# stm32_schematic.net
KiCad netlist of a schematic drawn in Altium Designer
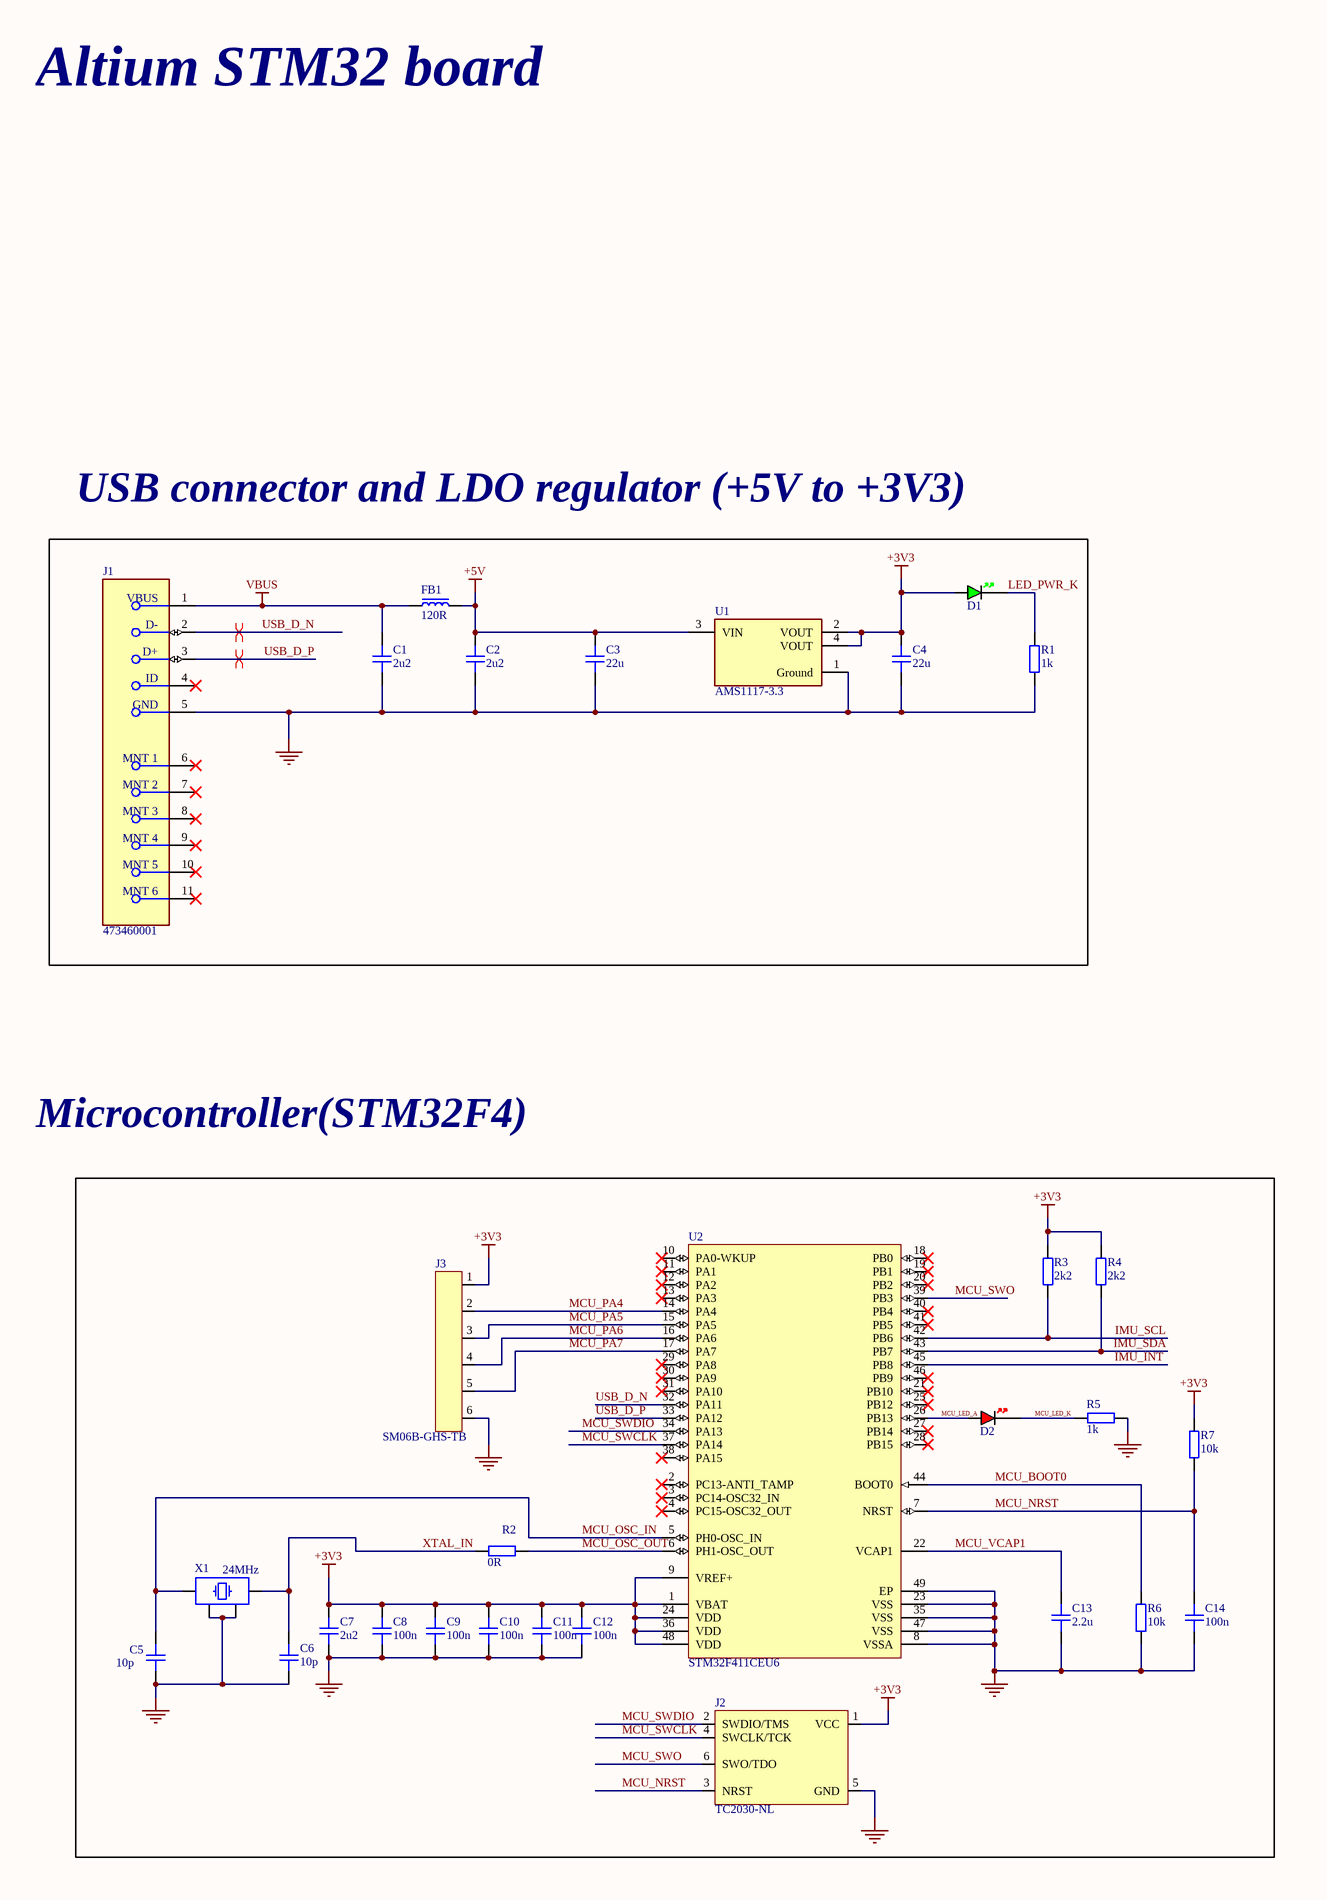
[diagram p0: stm32_schematic.SchDoc, left]
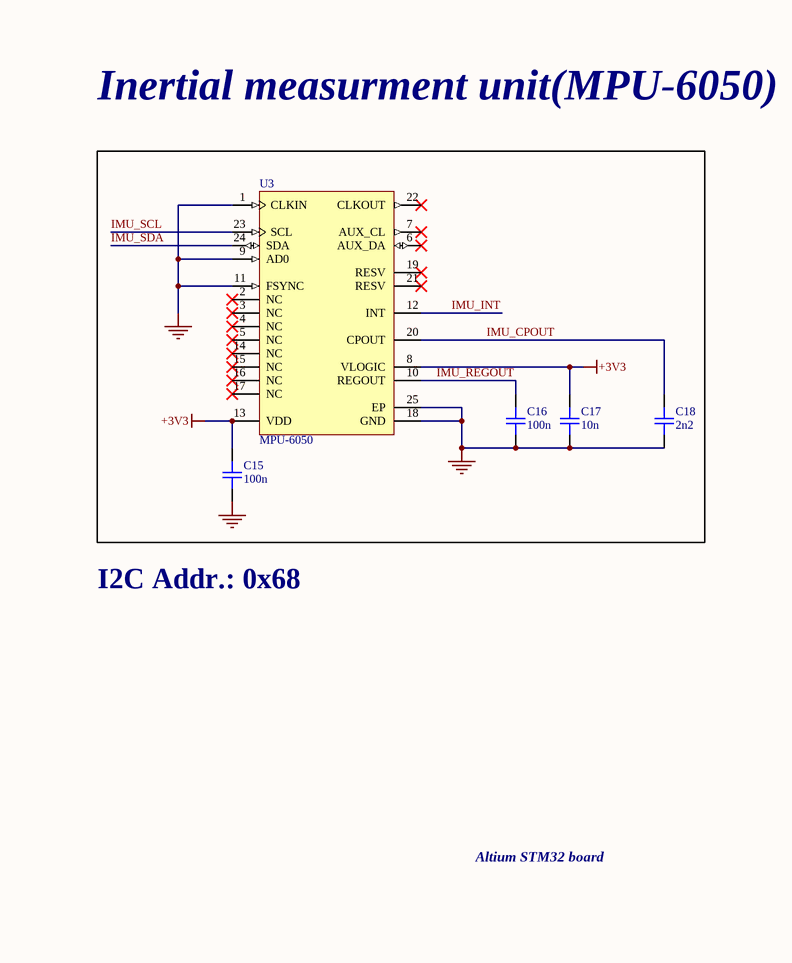
[diagram p1: stm32_schematic.SchDoc, right]

(export (version "E")
  (design (tool "Eeschema 10.0.6"))
  (components
    (comp (ref "C1")
      (value "2u2")
      (footprint "CAP_0603")
      (description "Capacitor SMD 0603")
      (libsource (lib "Schematic-Lib-PhilsLab") (part "CAP_0603"))
    )
    (comp (ref "C2")
      (value "2u2")
      (footprint "CAP_0603")
      (description "Capacitor SMD 0603")
      (libsource (lib "Schematic-Lib-PhilsLab") (part "CAP_0603"))
    )
    (comp (ref "C3")
      (value "22u")
      (footprint "CAP_0805")
      (description "Capacitor SMD 0805")
      (libsource (lib "Schematic-Lib-PhilsLab") (part "CAP_0805"))
    )
    (comp (ref "C4")
      (value "22u")
      (footprint "CAP_0805")
      (description "Capacitor SMD 0805")
      (libsource (lib "Schematic-Lib-PhilsLab") (part "CAP_0805"))
    )
    (comp (ref "C5")
      (value "10p")
      (footprint "CAP_0402")
      (description "Capacitor SMD 0402")
      (libsource (lib "Schematic-Lib-PhilsLab") (part "CAP_0402"))
    )
    (comp (ref "C6")
      (value "10p")
      (footprint "CAP_0402")
      (description "Capacitor SMD 0402")
      (libsource (lib "Schematic-Lib-PhilsLab") (part "CAP_0402"))
    )
    (comp (ref "C7")
      (value "2u2")
      (footprint "CAP_0603")
      (description "Capacitor SMD 0603")
      (libsource (lib "Schematic-Lib-PhilsLab") (part "CAP_0603"))
    )
    (comp (ref "C8")
      (value "100n")
      (footprint "CAP_0402")
      (description "Capacitor SMD 0402")
      (libsource (lib "Schematic-Lib-PhilsLab") (part "CAP_0402"))
    )
    (comp (ref "C9")
      (value "100n")
      (footprint "CAP_0402")
      (description "Capacitor SMD 0402")
      (libsource (lib "Schematic-Lib-PhilsLab") (part "CAP_0402"))
    )
    (comp (ref "C10")
      (value "100n")
      (footprint "CAP_0402")
      (description "Capacitor SMD 0402")
      (libsource (lib "Schematic-Lib-PhilsLab") (part "CAP_0402"))
    )
    (comp (ref "C11")
      (value "100n")
      (footprint "CAP_0402")
      (description "Capacitor SMD 0402")
      (libsource (lib "Schematic-Lib-PhilsLab") (part "CAP_0402"))
    )
    (comp (ref "C12")
      (value "100n")
      (footprint "CAP_0402")
      (description "Capacitor SMD 0402")
      (libsource (lib "Schematic-Lib-PhilsLab") (part "CAP_0402"))
    )
    (comp (ref "C13")
      (value "2.2u")
      (footprint "CAP_0603")
      (description "Capacitor SMD 0603")
      (libsource (lib "Schematic-Lib-PhilsLab") (part "CAP_0603"))
    )
    (comp (ref "C14")
      (value "100n")
      (footprint "CAP_0402")
      (description "Capacitor SMD 0402")
      (libsource (lib "Schematic-Lib-PhilsLab") (part "CAP_0402"))
    )
    (comp (ref "C15")
      (value "100n")
      (footprint "CAP_0402")
      (description "Capacitor SMD 0402")
      (libsource (lib "Schematic-Lib-PhilsLab") (part "CAP_0402"))
    )
    (comp (ref "C16")
      (value "100n")
      (footprint "CAP_0402")
      (description "Capacitor SMD 0402")
      (libsource (lib "Schematic-Lib-PhilsLab") (part "CAP_0402"))
    )
    (comp (ref "C17")
      (value "10n")
      (footprint "CAP_0402")
      (description "Capacitor SMD 0402")
      (libsource (lib "Schematic-Lib-PhilsLab") (part "CAP_0402"))
    )
    (comp (ref "C18")
      (value "2n2")
      (footprint "CAP_0402")
      (description "Capacitor SMD 0402")
      (libsource (lib "Schematic-Lib-PhilsLab") (part "CAP_0402"))
    )
    (comp (ref "D1")
      (value "GREEN")
      (footprint "LED_0402_GREEN")
      (description "LED 0402 GREEN SMD")
      (libsource (lib "Schematic-Lib-PhilsLab") (part "LED_0402_GREEN"))
    )
    (comp (ref "D2")
      (value "RED")
      (footprint "LED_0402_RED")
      (description "LED 0402 RED SMD")
      (libsource (lib "Schematic-Lib-PhilsLab") (part "LED_0402_RED"))
    )
    (comp (ref "FB1")
      (value "120R")
      (footprint "FB_0603")
      (description "Ferrite Bead SMD 0603")
      (libsource (lib "Schematic-Lib-PhilsLab") (part "FB_0603"))
    )
    (comp (ref "J1")
      (value "473460001")
      (footprint "FP-473460001-MFG")
      (description "CONN RCPT USB2.0 MICRO B SMD R/A")
      (fields
        (field (name "OCTOPART") "https://octopart.com/47346-0001-molex-7164928")
        (field (name "MANUFACTURER") "Molex")
      )
      (libsource (lib "Altium Content Vault") (part "53ae1f1d9b557310b43ca686e5bb76a"))
    )
    (comp (ref "J2")
      (value "TC2030-NL")
      (footprint "TC2030-NL-FP")
      (description "Tag-Connect No-Solder SWD Debug Connector (No Legs) DO NOT PLACE")
      (fields
        (field (name "MANUFACTURER") "Tag-Connect")
        (field (name "MANUFACTURER PART NUMBER") "TC2030-NL-FP")
      )
      (libsource (lib "Schematic-Lib-PhilsLab") (part "TC2030-NL"))
    )
    (comp (ref "J3")
      (value "SM06B-GHS-TB")
      (footprint "SM06B-GHS-TB")
      (description "Header Connector 6 Position 1.25MM Pitch SMD Horizontal JST GH")
      (fields (field (name "MANUFACTURER") "JST"))
      (libsource (lib "Schematic-Lib-PhilsLab") (part "SM06B-GHS-TB"))
    )
    (comp (ref "R1")
      (value "1k")
      (footprint "RES_0402")
      (description "Resistor SMD 0402")
      (libsource (lib "Schematic-Lib-PhilsLab") (part "RES_0402"))
    )
    (comp (ref "R2")
      (value "0R")
      (footprint "RES_0402")
      (description "Resistor SMD 0402")
      (libsource (lib "Schematic-Lib-PhilsLab") (part "RES_0402"))
    )
    (comp (ref "R3")
      (value "2k2")
      (footprint "RES_0402")
      (description "Resistor SMD 0402")
      (libsource (lib "Schematic-Lib-PhilsLab") (part "RES_0402"))
    )
    (comp (ref "R4")
      (value "2k2")
      (footprint "RES_0402")
      (description "Resistor SMD 0402")
      (libsource (lib "Schematic-Lib-PhilsLab") (part "RES_0402"))
    )
    (comp (ref "R5")
      (value "1k")
      (footprint "RES_0402")
      (description "Resistor SMD 0402")
      (libsource (lib "Schematic-Lib-PhilsLab") (part "RES_0402"))
    )
    (comp (ref "R6")
      (value "10k")
      (footprint "RES_0402")
      (description "Resistor SMD 0402")
      (libsource (lib "Schematic-Lib-PhilsLab") (part "RES_0402"))
    )
    (comp (ref "R7")
      (value "10k")
      (footprint "RES_0402")
      (description "Resistor SMD 0402")
      (libsource (lib "Schematic-Lib-PhilsLab") (part "RES_0402"))
    )
    (comp (ref "U1")
      (value "AMS1117-3.3")
      (footprint "FP-AMS1117-IPC_C")
      (description "LDO Voltage Regulators 1A, 3.3V")
      (fields
        (field (name "OCTOPART") "https://octopart.com/ams1117-3.3-advanced+monolithic+systems-25899300")
        (field (name "MANUFACTURER") "Advanced Monolithic Systems")
      )
      (libsource (lib "Altium Content Vault") (part "8bdbb5f8e77002000e30dd2845d0354"))
    )
    (comp (ref "U2")
      (value "STM32F411CEU6")
      (footprint "STM-UFQFPN48_L")
      (libsource (lib "Altium Content Vault") (part "MC-ARM-STM32F411-UFQFPN48"))
    )
    (comp (ref "U3")
      (value "MPU-6050")
      (footprint "IS-QFN-24_V")
      (fields (field (name "MANUFACTURER") "InvenSense"))
      (libsource (lib "Altium Content Vault") (part "IS-MPU-6050-QFN-24"))
    )
    (comp (ref "X1")
      (value "24MHz")
      (footprint "XTAL_3225")
      (description "Crystal SMD 24MHz 10PPM 7pF 3225")
      (fields
        (field (name "MANUFACTURER") "Epson")
        (field (name "MANUFACTURER PART NUMBER") "TSX-3225 24.0000MF15X-AC")
      )
      (libsource (lib "Schematic-Lib-PhilsLab") (part "TSX-3225_24.0000MF15X-AC"))
    )
  )
  (nets
    (net (code "1") (name "+3V3") (class "Default")
      (node (ref "C10") (pin "2") (pinfunction "2_2") (pintype "passive"))
      (node (ref "C11") (pin "2") (pinfunction "2_2") (pintype "passive"))
      (node (ref "C12") (pin "2") (pinfunction "2_2") (pintype "passive"))
      (node (ref "C15") (pin "2") (pinfunction "2_2") (pintype "passive"))
      (node (ref "C17") (pin "2") (pinfunction "2_2") (pintype "passive"))
      (node (ref "C4") (pin "2") (pinfunction "2_2") (pintype "passive"))
      (node (ref "C7") (pin "2") (pinfunction "2_2") (pintype "passive"))
      (node (ref "C8") (pin "2") (pinfunction "2_2") (pintype "passive"))
      (node (ref "C9") (pin "2") (pinfunction "2_2") (pintype "passive"))
      (node (ref "D1") (pin "A") (pinfunction "A_A") (pintype "passive"))
      (node (ref "J2") (pin "1") (pinfunction "VCC_1") (pintype "passive"))
      (node (ref "J3") (pin "1") (pinfunction "1_1") (pintype "passive"))
      (node (ref "R3") (pin "2") (pinfunction "2_2") (pintype "passive"))
      (node (ref "R4") (pin "2") (pinfunction "2_2") (pintype "passive"))
      (node (ref "R7") (pin "2") (pinfunction "2_2") (pintype "passive"))
      (node (ref "U1") (pin "2") (pinfunction "VOUT_2") (pintype "passive"))
      (node (ref "U1") (pin "4") (pinfunction "VOUT_4") (pintype "passive"))
      (node (ref "U2") (pin "1") (pinfunction "VBAT_1") (pintype "power_in"))
      (node (ref "U2") (pin "24") (pinfunction "VDD_24") (pintype "power_in"))
      (node (ref "U2") (pin "36") (pinfunction "VDD_36") (pintype "power_in"))
      (node (ref "U2") (pin "48") (pinfunction "VDD_48") (pintype "power_in"))
      (node (ref "U2") (pin "9") (pinfunction "VREF+_9") (pintype "power_in"))
      (node (ref "U3") (pin "13") (pinfunction "VDD_13") (pintype "power_in"))
      (node (ref "U3") (pin "8") (pinfunction "VLOGIC_8") (pintype "power_in"))
    )
    (net (code "2") (name "+5V") (class "Default")
      (node (ref "C2") (pin "2") (pinfunction "2_2") (pintype "passive"))
      (node (ref "C3") (pin "2") (pinfunction "2_2") (pintype "passive"))
      (node (ref "FB1") (pin "2") (pinfunction "2_2") (pintype "passive"))
      (node (ref "U1") (pin "3") (pinfunction "VIN_3") (pintype "power_in"))
    )
    (net (code "4") (name "/IMU_CPOUT") (class "Default")
      (node (ref "C18") (pin "2") (pinfunction "2_2") (pintype "passive"))
      (node (ref "U3") (pin "20") (pinfunction "CPOUT_20") (pintype "passive"))
    )
    (net (code "5") (name "/IMU_INT") (class "Default")
      (node (ref "U2") (pin "45") (pinfunction "PB8_45") (pintype "bidirectional"))
      (node (ref "U3") (pin "12") (pinfunction "INT_12") (pintype "open_collector"))
    )
    (net (code "6") (name "/IMU_REGOUT") (class "Default")
      (node (ref "C16") (pin "2") (pinfunction "2_2") (pintype "passive"))
      (node (ref "U3") (pin "10") (pinfunction "REGOUT_10") (pintype "passive"))
    )
    (net (code "7") (name "/IMU_SCL") (class "Default")
      (node (ref "R3") (pin "1") (pinfunction "1_1") (pintype "passive"))
      (node (ref "U2") (pin "42") (pinfunction "PB6_42") (pintype "bidirectional"))
      (node (ref "U3") (pin "23") (pinfunction "SCL_23") (pintype "input"))
    )
    (net (code "8") (name "/IMU_SDA") (class "Default")
      (node (ref "R4") (pin "1") (pinfunction "1_1") (pintype "passive"))
      (node (ref "U2") (pin "43") (pinfunction "PB7_43") (pintype "bidirectional"))
      (node (ref "U3") (pin "24") (pinfunction "SDA_24") (pintype "bidirectional"))
    )
    (net (code "9") (name "/LED_PWR_K") (class "Default")
      (node (ref "D1") (pin "K") (pinfunction "K_K") (pintype "passive"))
      (node (ref "R1") (pin "2") (pinfunction "2_2") (pintype "passive"))
    )
    (net (code "10") (name "/MCU_BOOT0") (class "Default")
      (node (ref "R6") (pin "2") (pinfunction "2_2") (pintype "passive"))
      (node (ref "U2") (pin "44") (pinfunction "BOOT0_44") (pintype "input"))
    )
    (net (code "11") (name "/MCU_LED_A") (class "Default")
      (node (ref "D2") (pin "A") (pinfunction "A_A") (pintype "passive"))
      (node (ref "U2") (pin "26") (pinfunction "PB13_26") (pintype "bidirectional"))
    )
    (net (code "12") (name "/MCU_LED_K") (class "Default")
      (node (ref "D2") (pin "K") (pinfunction "K_K") (pintype "passive"))
      (node (ref "R5") (pin "2") (pinfunction "2_2") (pintype "passive"))
    )
    (net (code "13") (name "/MCU_NRST") (class "Default")
      (node (ref "C14") (pin "2") (pinfunction "2_2") (pintype "passive"))
      (node (ref "J2") (pin "3") (pinfunction "NRST_3") (pintype "passive"))
      (node (ref "R7") (pin "1") (pinfunction "1_1") (pintype "passive"))
      (node (ref "U2") (pin "7") (pinfunction "NRST_7") (pintype "bidirectional"))
    )
    (net (code "14") (name "/MCU_OSC_IN") (class "Default")
      (node (ref "C5") (pin "2") (pinfunction "2_2") (pintype "passive"))
      (node (ref "U2") (pin "5") (pinfunction "PH0-OSC_IN_5") (pintype "bidirectional"))
      (node (ref "X1") (pin "1") (pinfunction "1_1") (pintype "passive"))
    )
    (net (code "15") (name "/MCU_OSC_OUT") (class "Default")
      (node (ref "R2") (pin "2") (pinfunction "2_2") (pintype "passive"))
      (node (ref "U2") (pin "6") (pinfunction "PH1-OSC_OUT_6") (pintype "bidirectional"))
    )
    (net (code "16") (name "/MCU_PA4") (class "Default")
      (node (ref "J3") (pin "2") (pinfunction "2_2") (pintype "passive"))
      (node (ref "U2") (pin "14") (pinfunction "PA4_14") (pintype "bidirectional"))
    )
    (net (code "17") (name "/MCU_PA5") (class "Default")
      (node (ref "J3") (pin "3") (pinfunction "3_3") (pintype "passive"))
      (node (ref "U2") (pin "15") (pinfunction "PA5_15") (pintype "bidirectional"))
    )
    (net (code "18") (name "/MCU_PA6") (class "Default")
      (node (ref "J3") (pin "4") (pinfunction "4_4") (pintype "passive"))
      (node (ref "U2") (pin "16") (pinfunction "PA6_16") (pintype "bidirectional"))
    )
    (net (code "19") (name "/MCU_PA7") (class "Default")
      (node (ref "J3") (pin "5") (pinfunction "5_5") (pintype "passive"))
      (node (ref "U2") (pin "17") (pinfunction "PA7_17") (pintype "bidirectional"))
    )
    (net (code "20") (name "/MCU_SWCLK") (class "Default")
      (node (ref "J2") (pin "4") (pinfunction "SWCLK/TCK_4") (pintype "passive"))
      (node (ref "U2") (pin "37") (pinfunction "PA14_37") (pintype "bidirectional"))
    )
    (net (code "21") (name "/MCU_SWDIO") (class "Default")
      (node (ref "J2") (pin "2") (pinfunction "SWDIO/TMS_2") (pintype "passive"))
      (node (ref "U2") (pin "34") (pinfunction "PA13_34") (pintype "bidirectional"))
    )
    (net (code "22") (name "/MCU_SWO") (class "Default")
      (node (ref "J2") (pin "6") (pinfunction "SWO/TDO_6") (pintype "passive"))
      (node (ref "U2") (pin "39") (pinfunction "PB3_39") (pintype "bidirectional"))
    )
    (net (code "23") (name "/MCU_VCAP1") (class "Default")
      (node (ref "C13") (pin "2") (pinfunction "2_2") (pintype "passive"))
      (node (ref "U2") (pin "22") (pinfunction "VCAP1_22") (pintype "passive"))
    )
    (net (code "24") (name "/USB_D_N") (class "Default")
      (node (ref "J1") (pin "2") (pinfunction "D-_2") (pintype "bidirectional"))
      (node (ref "U2") (pin "32") (pinfunction "PA11_32") (pintype "bidirectional"))
    )
    (net (code "25") (name "/USB_D_P") (class "Default")
      (node (ref "J1") (pin "3") (pinfunction "D+_3") (pintype "bidirectional"))
      (node (ref "U2") (pin "33") (pinfunction "PA12_33") (pintype "bidirectional"))
    )
    (net (code "26") (name "/XTAL_IN") (class "Default")
      (node (ref "C6") (pin "2") (pinfunction "2_2") (pintype "passive"))
      (node (ref "R2") (pin "1") (pinfunction "1_1") (pintype "passive"))
      (node (ref "X1") (pin "3") (pinfunction "3_3") (pintype "passive"))
    )
    (net (code "27") (name "GND") (class "Default")
      (node (ref "C1") (pin "1") (pinfunction "1_1") (pintype "passive"))
      (node (ref "C10") (pin "1") (pinfunction "1_1") (pintype "passive"))
      (node (ref "C11") (pin "1") (pinfunction "1_1") (pintype "passive"))
      (node (ref "C12") (pin "1") (pinfunction "1_1") (pintype "passive"))
      (node (ref "C13") (pin "1") (pinfunction "1_1") (pintype "passive"))
      (node (ref "C14") (pin "1") (pinfunction "1_1") (pintype "passive"))
      (node (ref "C15") (pin "1") (pinfunction "1_1") (pintype "passive"))
      (node (ref "C16") (pin "1") (pinfunction "1_1") (pintype "passive"))
      (node (ref "C17") (pin "1") (pinfunction "1_1") (pintype "passive"))
      (node (ref "C18") (pin "1") (pinfunction "1_1") (pintype "passive"))
      (node (ref "C2") (pin "1") (pinfunction "1_1") (pintype "passive"))
      (node (ref "C3") (pin "1") (pinfunction "1_1") (pintype "passive"))
      (node (ref "C4") (pin "1") (pinfunction "1_1") (pintype "passive"))
      (node (ref "C5") (pin "1") (pinfunction "1_1") (pintype "passive"))
      (node (ref "C6") (pin "1") (pinfunction "1_1") (pintype "passive"))
      (node (ref "C7") (pin "1") (pinfunction "1_1") (pintype "passive"))
      (node (ref "C8") (pin "1") (pinfunction "1_1") (pintype "passive"))
      (node (ref "C9") (pin "1") (pinfunction "1_1") (pintype "passive"))
      (node (ref "J1") (pin "5") (pinfunction "GND_5") (pintype "power_in"))
      (node (ref "J2") (pin "5") (pinfunction "GND_5") (pintype "passive"))
      (node (ref "J3") (pin "6") (pinfunction "6_6") (pintype "passive"))
      (node (ref "R1") (pin "1") (pinfunction "1_1") (pintype "passive"))
      (node (ref "R5") (pin "1") (pinfunction "1_1") (pintype "passive"))
      (node (ref "R6") (pin "1") (pinfunction "1_1") (pintype "passive"))
      (node (ref "U1") (pin "1") (pinfunction "Ground_1") (pintype "power_in"))
      (node (ref "U2") (pin "23") (pinfunction "VSS_23") (pintype "power_in"))
      (node (ref "U2") (pin "35") (pinfunction "VSS_35") (pintype "power_in"))
      (node (ref "U2") (pin "47") (pinfunction "VSS_47") (pintype "power_in"))
      (node (ref "U2") (pin "49") (pinfunction "EP_49") (pintype "power_in"))
      (node (ref "U2") (pin "8") (pinfunction "VSSA_8") (pintype "power_in"))
      (node (ref "U3") (pin "1") (pinfunction "CLKIN_1") (pintype "input"))
      (node (ref "U3") (pin "11") (pinfunction "FSYNC_11") (pintype "input"))
      (node (ref "U3") (pin "18") (pinfunction "GND_18") (pintype "power_in"))
      (node (ref "U3") (pin "25") (pinfunction "EP_25") (pintype "power_in"))
      (node (ref "U3") (pin "9") (pinfunction "AD0_9") (pintype "input"))
      (node (ref "X1") (pin "2") (pinfunction "2_2") (pintype "passive"))
      (node (ref "X1") (pin "4") (pinfunction "4_4") (pintype "passive"))
    )
    (net (code "28") (name "VBUS") (class "Default")
      (node (ref "C1") (pin "2") (pinfunction "2_2") (pintype "passive"))
      (node (ref "FB1") (pin "1") (pinfunction "1_1") (pintype "passive"))
      (node (ref "J1") (pin "1") (pinfunction "VBUS_1") (pintype "power_in"))
    )
    (net (code "29") (name "unconnected-(J1-ID-Pad4)") (class "Default")
      (node (ref "J1") (pin "4") (pinfunction "ID_4") (pintype "passive+no_connect"))
    )
    (net (code "30") (name "unconnected-(J1-MNT_1-Pad6)") (class "Default")
      (node (ref "J1") (pin "6") (pinfunction "MNT_1_6") (pintype "passive+no_connect"))
    )
    (net (code "31") (name "unconnected-(J1-MNT_2-Pad7)") (class "Default")
      (node (ref "J1") (pin "7") (pinfunction "MNT_2_7") (pintype "passive+no_connect"))
    )
    (net (code "32") (name "unconnected-(J1-MNT_3-Pad8)") (class "Default")
      (node (ref "J1") (pin "8") (pinfunction "MNT_3_8") (pintype "passive+no_connect"))
    )
    (net (code "33") (name "unconnected-(J1-MNT_4-Pad9)") (class "Default")
      (node (ref "J1") (pin "9") (pinfunction "MNT_4_9") (pintype "passive+no_connect"))
    )
    (net (code "34") (name "unconnected-(J1-MNT_5-Pad10)") (class "Default")
      (node (ref "J1") (pin "10") (pinfunction "MNT_5_10") (pintype "passive+no_connect"))
    )
    (net (code "35") (name "unconnected-(J1-MNT_6-Pad11)") (class "Default")
      (node (ref "J1") (pin "11") (pinfunction "MNT_6_11") (pintype "passive+no_connect"))
    )
    (net (code "36") (name "unconnected-(U2-PA0-WKUP-Pad10)") (class "Default")
      (node (ref "U2") (pin "10") (pinfunction "PA0-WKUP_10") (pintype "bidirectional+no_connect"))
    )
    (net (code "37") (name "unconnected-(U2-PA1-Pad11)") (class "Default")
      (node (ref "U2") (pin "11") (pinfunction "PA1_11") (pintype "bidirectional+no_connect"))
    )
    (net (code "38") (name "unconnected-(U2-PA2-Pad12)") (class "Default")
      (node (ref "U2") (pin "12") (pinfunction "PA2_12") (pintype "bidirectional+no_connect"))
    )
    (net (code "39") (name "unconnected-(U2-PA3-Pad13)") (class "Default")
      (node (ref "U2") (pin "13") (pinfunction "PA3_13") (pintype "bidirectional+no_connect"))
    )
    (net (code "40") (name "unconnected-(U2-PA8-Pad29)") (class "Default")
      (node (ref "U2") (pin "29") (pinfunction "PA8_29") (pintype "bidirectional+no_connect"))
    )
    (net (code "41") (name "unconnected-(U2-PA9-Pad30)") (class "Default")
      (node (ref "U2") (pin "30") (pinfunction "PA9_30") (pintype "bidirectional+no_connect"))
    )
    (net (code "42") (name "unconnected-(U2-PA10-Pad31)") (class "Default")
      (node (ref "U2") (pin "31") (pinfunction "PA10_31") (pintype "bidirectional+no_connect"))
    )
    (net (code "43") (name "unconnected-(U2-PA15-Pad38)") (class "Default")
      (node (ref "U2") (pin "38") (pinfunction "PA15_38") (pintype "bidirectional+no_connect"))
    )
    (net (code "44") (name "unconnected-(U2-PB0-Pad18)") (class "Default")
      (node (ref "U2") (pin "18") (pinfunction "PB0_18") (pintype "bidirectional+no_connect"))
    )
    (net (code "45") (name "unconnected-(U2-PB1-Pad19)") (class "Default")
      (node (ref "U2") (pin "19") (pinfunction "PB1_19") (pintype "bidirectional+no_connect"))
    )
    (net (code "46") (name "unconnected-(U2-PB2-Pad20)") (class "Default")
      (node (ref "U2") (pin "20") (pinfunction "PB2_20") (pintype "bidirectional+no_connect"))
    )
    (net (code "47") (name "unconnected-(U2-PB4-Pad40)") (class "Default")
      (node (ref "U2") (pin "40") (pinfunction "PB4_40") (pintype "bidirectional+no_connect"))
    )
    (net (code "48") (name "unconnected-(U2-PB5-Pad41)") (class "Default")
      (node (ref "U2") (pin "41") (pinfunction "PB5_41") (pintype "bidirectional+no_connect"))
    )
    (net (code "49") (name "unconnected-(U2-PB9-Pad46)") (class "Default")
      (node (ref "U2") (pin "46") (pinfunction "PB9_46") (pintype "bidirectional+no_connect"))
    )
    (net (code "50") (name "unconnected-(U2-PB10-Pad21)") (class "Default")
      (node (ref "U2") (pin "21") (pinfunction "PB10_21") (pintype "bidirectional+no_connect"))
    )
    (net (code "51") (name "unconnected-(U2-PB12-Pad25)") (class "Default")
      (node (ref "U2") (pin "25") (pinfunction "PB12_25") (pintype "bidirectional+no_connect"))
    )
    (net (code "52") (name "unconnected-(U2-PB14-Pad27)") (class "Default")
      (node (ref "U2") (pin "27") (pinfunction "PB14_27") (pintype "bidirectional+no_connect"))
    )
    (net (code "53") (name "unconnected-(U2-PB15-Pad28)") (class "Default")
      (node (ref "U2") (pin "28") (pinfunction "PB15_28") (pintype "bidirectional+no_connect"))
    )
    (net (code "54") (name "unconnected-(U2-PC13-ANTI_TAMP-Pad2)") (class "Default")
      (node (ref "U2") (pin "2") (pinfunction "PC13-ANTI_TAMP_2") (pintype "bidirectional+no_connect"))
    )
    (net (code "55") (name "unconnected-(U2-PC14-OSC32_IN-Pad3)") (class "Default")
      (node (ref "U2") (pin "3") (pinfunction "PC14-OSC32_IN_3") (pintype "bidirectional+no_connect"))
    )
    (net (code "56") (name "unconnected-(U2-PC15-OSC32_OUT-Pad4)") (class "Default")
      (node (ref "U2") (pin "4") (pinfunction "PC15-OSC32_OUT_4") (pintype "bidirectional+no_connect"))
    )
    (net (code "57") (name "unconnected-(U3-AUX_CL-Pad7)") (class "Default")
      (node (ref "U3") (pin "7") (pinfunction "AUX_CL_7") (pintype "output+no_connect"))
    )
    (net (code "58") (name "unconnected-(U3-AUX_DA-Pad6)") (class "Default")
      (node (ref "U3") (pin "6") (pinfunction "AUX_DA_6") (pintype "bidirectional+no_connect"))
    )
    (net (code "59") (name "unconnected-(U3-CLKOUT-Pad22)") (class "Default")
      (node (ref "U3") (pin "22") (pinfunction "CLKOUT_22") (pintype "output+no_connect"))
    )
    (net (code "60") (name "unconnected-(U3-NC-Pad2)") (class "Default")
      (node (ref "U3") (pin "2") (pinfunction "NC_2") (pintype "passive+no_connect"))
    )
    (net (code "61") (name "unconnected-(U3-NC-Pad3)") (class "Default")
      (node (ref "U3") (pin "3") (pinfunction "NC_3") (pintype "passive+no_connect"))
    )
    (net (code "62") (name "unconnected-(U3-NC-Pad4)") (class "Default")
      (node (ref "U3") (pin "4") (pinfunction "NC_4") (pintype "passive+no_connect"))
    )
    (net (code "63") (name "unconnected-(U3-NC-Pad5)") (class "Default")
      (node (ref "U3") (pin "5") (pinfunction "NC_5") (pintype "passive+no_connect"))
    )
    (net (code "64") (name "unconnected-(U3-NC-Pad14)") (class "Default")
      (node (ref "U3") (pin "14") (pinfunction "NC_14") (pintype "passive+no_connect"))
    )
    (net (code "65") (name "unconnected-(U3-NC-Pad15)") (class "Default")
      (node (ref "U3") (pin "15") (pinfunction "NC_15") (pintype "passive+no_connect"))
    )
    (net (code "66") (name "unconnected-(U3-NC-Pad16)") (class "Default")
      (node (ref "U3") (pin "16") (pinfunction "NC_16") (pintype "passive+no_connect"))
    )
    (net (code "67") (name "unconnected-(U3-NC-Pad17)") (class "Default")
      (node (ref "U3") (pin "17") (pinfunction "NC_17") (pintype "passive+no_connect"))
    )
    (net (code "68") (name "unconnected-(U3-RESV-Pad19)") (class "Default")
      (node (ref "U3") (pin "19") (pinfunction "RESV_19") (pintype "passive+no_connect"))
    )
    (net (code "69") (name "unconnected-(U3-RESV-Pad21)") (class "Default")
      (node (ref "U3") (pin "21") (pinfunction "RESV_21") (pintype "passive+no_connect"))
    )
  )
)
